# ENC_SW_Frontpanel.net
KiCad netlist of a schematic drawn in EAGLE
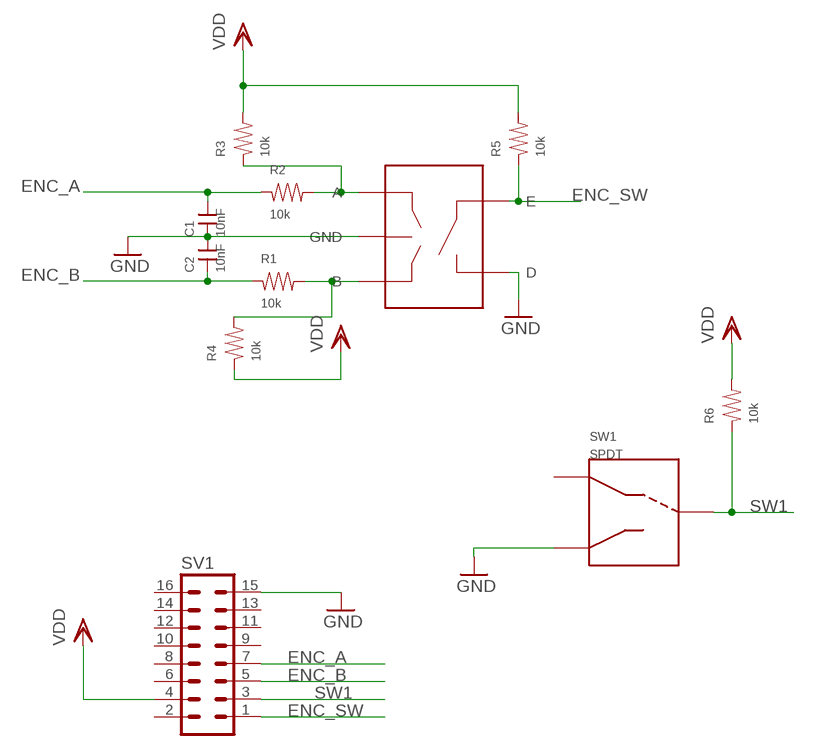
[diagram p0: schematic, sheet 1]

(export (version "E")
  (design (tool "Eeschema 10.0.6"))
  (components
    (comp (ref "C1")
      (value "10nF")
      (footprint "eagle-import:0603")
      (libsource (lib "eagle-import") (part "CAP0603"))
    )
    (comp (ref "C2")
      (value "10nF")
      (footprint "eagle-import:0603")
      (libsource (lib "eagle-import") (part "CAP0603"))
    )
    (comp (ref "ENC1")
      (value "PEC09")
      (footprint "eagle-import:PEC092320FS")
      (fields (field (name "PARTNO") "PEC09-2320F-S0015-ND"))
      (libsource (lib "eagle-import") (part "PEC09"))
    )
    (comp (ref "R1")
      (value "10k")
      (footprint "eagle-import:0603")
      (libsource (lib "eagle-import") (part "RES0603"))
    )
    (comp (ref "R2")
      (value "10k")
      (footprint "eagle-import:0603")
      (libsource (lib "eagle-import") (part "RES0603"))
    )
    (comp (ref "R3")
      (value "10k")
      (footprint "eagle-import:0603")
      (libsource (lib "eagle-import") (part "RES0603"))
    )
    (comp (ref "R4")
      (value "10k")
      (footprint "eagle-import:0603")
      (libsource (lib "eagle-import") (part "RES0603"))
    )
    (comp (ref "R5")
      (value "10k")
      (footprint "eagle-import:0603")
      (libsource (lib "eagle-import") (part "RES0603"))
    )
    (comp (ref "R6")
      (value "10k")
      (footprint "eagle-import:0603")
      (libsource (lib "eagle-import") (part "RES0603"))
    )
    (comp (ref "SV1")
      (value "ML16")
      (footprint "eagle-import:ML16")
      (libsource (lib "eagle-import") (part "ML16"))
    )
    (comp (ref "SW1")
      (value "SPDT")
      (footprint "eagle-import:100SP1-M7")
      (fields (field (name "PARTNUM") "100SP1T1B1M7QE-ND"))
      (libsource (lib "eagle-import") (part "SPDT"))
    )
  )
  (nets
    (net (code "1") (name "/ENC_A") (class "Default")
      (node (ref "C1") (pin "2") (pinfunction "P$2_2") (pintype "passive"))
      (node (ref "R2") (pin "1") (pinfunction "P$1_1") (pintype "passive"))
      (node (ref "SV1") (pin "7") (pinfunction "7_7") (pintype "passive"))
    )
    (net (code "2") (name "/ENC_B") (class "Default")
      (node (ref "C2") (pin "1") (pinfunction "P$1_1") (pintype "passive"))
      (node (ref "R1") (pin "1") (pinfunction "P$1_1") (pintype "passive"))
      (node (ref "SV1") (pin "5") (pinfunction "5_5") (pintype "passive"))
    )
    (net (code "3") (name "/ENC_SW") (class "Default")
      (node (ref "ENC1") (pin "E") (pinfunction "E_E") (pintype "bidirectional"))
      (node (ref "R5") (pin "1") (pinfunction "P$1_1") (pintype "passive"))
      (node (ref "SV1") (pin "1") (pinfunction "1_1") (pintype "passive"))
    )
    (net (code "4") (name "/SW1") (class "Default")
      (node (ref "R6") (pin "1") (pinfunction "P$1_1") (pintype "passive"))
      (node (ref "SV1") (pin "3") (pinfunction "3_3") (pintype "passive"))
      (node (ref "SW1") (pin "OUT") (pinfunction "OUT_OUT") (pintype "bidirectional"))
    )
    (net (code "5") (name "GND") (class "Default")
      (node (ref "C1") (pin "1") (pinfunction "P$1_1") (pintype "passive"))
      (node (ref "C2") (pin "2") (pinfunction "P$2_2") (pintype "passive"))
      (node (ref "ENC1") (pin "C") (pinfunction "GND_C") (pintype "bidirectional"))
      (node (ref "ENC1") (pin "D") (pinfunction "D_D") (pintype "bidirectional"))
      (node (ref "SV1") (pin "15") (pinfunction "15_15") (pintype "passive"))
      (node (ref "SW1") (pin "IN2") (pinfunction "IN2_IN2") (pintype "bidirectional"))
    )
    (net (code "6") (name "Net-(R1-P$2)") (class "Default")
      (node (ref "ENC1") (pin "B") (pinfunction "B_B") (pintype "bidirectional"))
      (node (ref "R1") (pin "2") (pinfunction "P$2_2") (pintype "passive"))
      (node (ref "R4") (pin "2") (pinfunction "P$2_2") (pintype "passive"))
    )
    (net (code "7") (name "Net-(R2-P$2)") (class "Default")
      (node (ref "ENC1") (pin "A") (pinfunction "A_A") (pintype "bidirectional"))
      (node (ref "R2") (pin "2") (pinfunction "P$2_2") (pintype "passive"))
      (node (ref "R3") (pin "1") (pinfunction "P$1_1") (pintype "passive"))
    )
    (net (code "8") (name "VDD") (class "Default")
      (node (ref "R3") (pin "2") (pinfunction "P$2_2") (pintype "passive"))
      (node (ref "R4") (pin "1") (pinfunction "P$1_1") (pintype "passive"))
      (node (ref "R5") (pin "2") (pinfunction "P$2_2") (pintype "passive"))
      (node (ref "R6") (pin "2") (pinfunction "P$2_2") (pintype "passive"))
      (node (ref "SV1") (pin "4") (pinfunction "4_4") (pintype "passive"))
    )
    (net (code "9") (name "unconnected-(SV1-Pad2)") (class "Default")
      (node (ref "SV1") (pin "2") (pinfunction "2_2") (pintype "passive"))
    )
    (net (code "10") (name "unconnected-(SV1-Pad6)") (class "Default")
      (node (ref "SV1") (pin "6") (pinfunction "6_6") (pintype "passive"))
    )
    (net (code "11") (name "unconnected-(SV1-Pad8)") (class "Default")
      (node (ref "SV1") (pin "8") (pinfunction "8_8") (pintype "passive"))
    )
    (net (code "12") (name "unconnected-(SV1-Pad9)") (class "Default")
      (node (ref "SV1") (pin "9") (pinfunction "9_9") (pintype "passive"))
    )
    (net (code "13") (name "unconnected-(SV1-Pad10)") (class "Default")
      (node (ref "SV1") (pin "10") (pinfunction "10_10") (pintype "passive"))
    )
    (net (code "14") (name "unconnected-(SV1-Pad11)") (class "Default")
      (node (ref "SV1") (pin "11") (pinfunction "11_11") (pintype "passive"))
    )
    (net (code "15") (name "unconnected-(SV1-Pad12)") (class "Default")
      (node (ref "SV1") (pin "12") (pinfunction "12_12") (pintype "passive"))
    )
    (net (code "16") (name "unconnected-(SV1-Pad13)") (class "Default")
      (node (ref "SV1") (pin "13") (pinfunction "13_13") (pintype "passive"))
    )
    (net (code "17") (name "unconnected-(SV1-Pad14)") (class "Default")
      (node (ref "SV1") (pin "14") (pinfunction "14_14") (pintype "passive"))
    )
    (net (code "18") (name "unconnected-(SV1-Pad16)") (class "Default")
      (node (ref "SV1") (pin "16") (pinfunction "16_16") (pintype "passive"))
    )
    (net (code "19") (name "unconnected-(SW1-PadIN1)") (class "Default")
      (node (ref "SW1") (pin "IN1") (pinfunction "IN1_IN1") (pintype "bidirectional"))
    )
  )
)
